# stepper_ctrl_v2.net
KiCad netlist of a schematic drawn in EAGLE
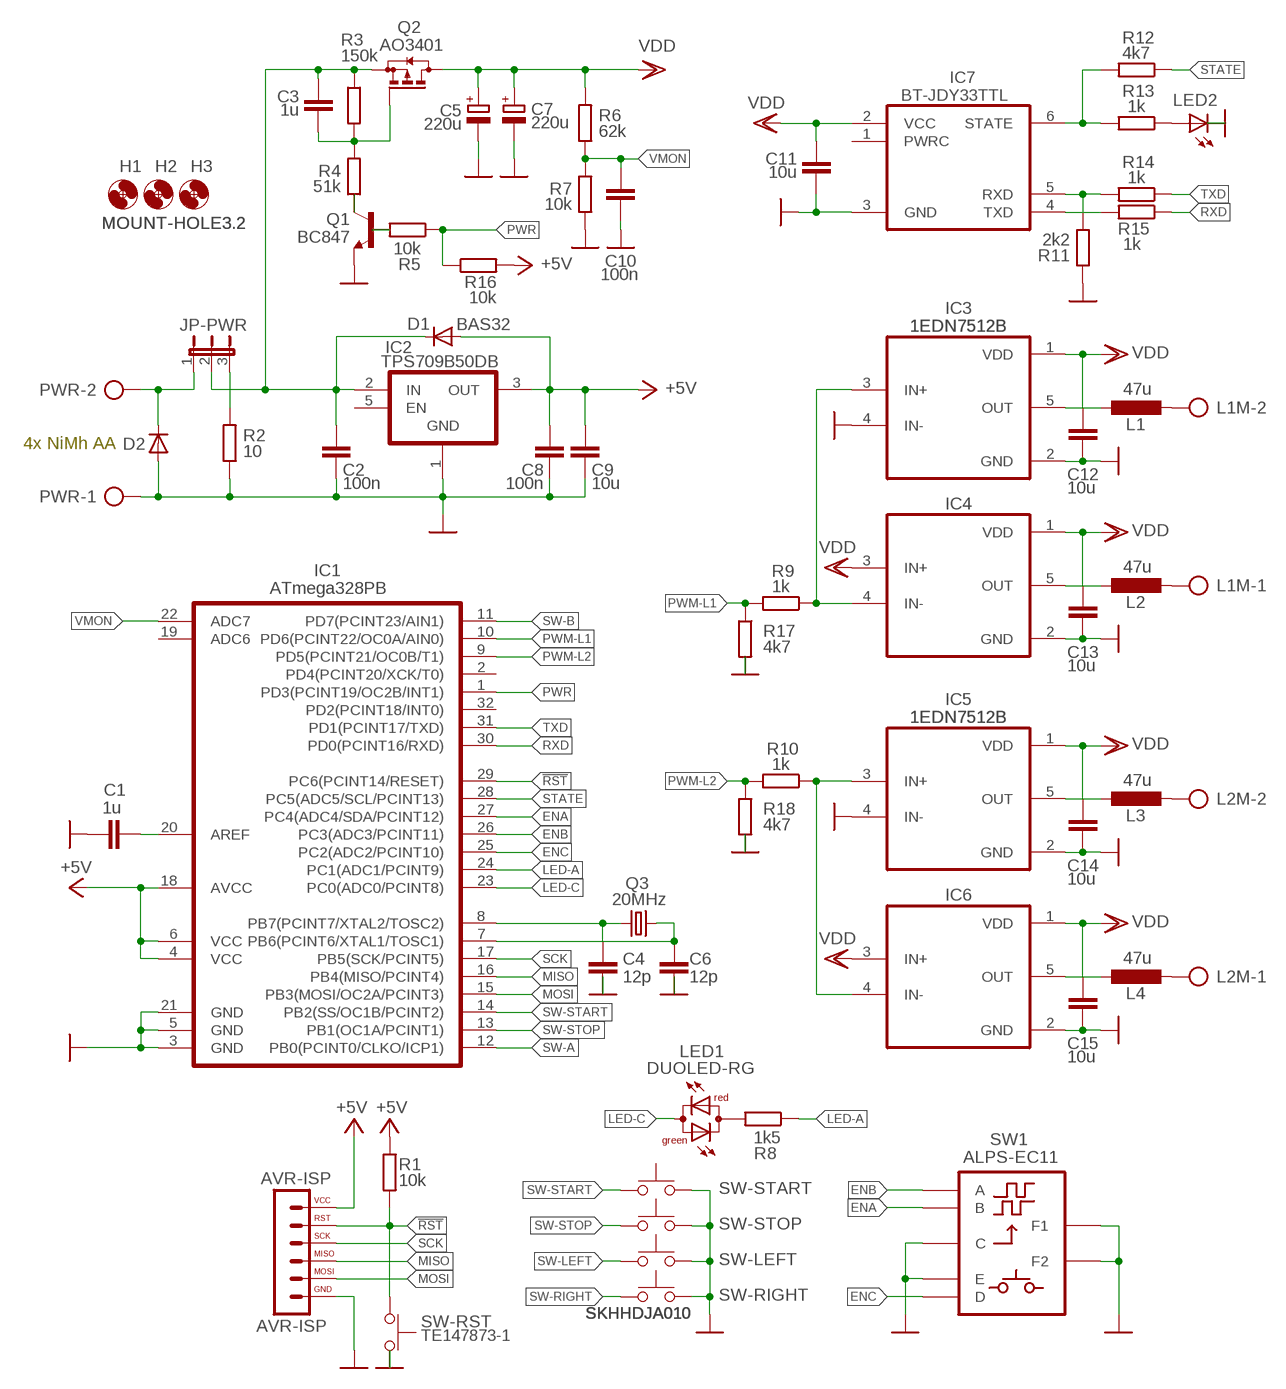
[diagram p0: schematic, sheet 1]

(export (version "E")
  (design (tool "Eeschema 10.0.6"))
  (components
    (comp (ref "AVR-ISP")
      (value "AVR-ISP")
      (footprint "eagle-import:SIL6-NNRND")
      (libsource (lib "eagle-import") (part "AVR_SPINR"))
    )
    (comp (ref "C1")
      (value "1u")
      (footprint "eagle-import:C0805K")
      (libsource (lib "eagle-import") (part "C-EUC0805K"))
    )
    (comp (ref "C2")
      (value "100n")
      (footprint "eagle-import:C0805K")
      (libsource (lib "eagle-import") (part "C-EUC0805K"))
    )
    (comp (ref "C3")
      (value "1u")
      (footprint "eagle-import:C0805K")
      (libsource (lib "eagle-import") (part "C-EUC0805K"))
    )
    (comp (ref "C4")
      (value "12p")
      (footprint "eagle-import:C0603K")
      (libsource (lib "eagle-import") (part "C-EUC0603K"))
    )
    (comp (ref "C5")
      (value "220u")
      (footprint "eagle-import:E2,5-6")
      (libsource (lib "eagle-import") (part "CPOL-EUE2.5-6"))
    )
    (comp (ref "C6")
      (value "12p")
      (footprint "eagle-import:C0603K")
      (libsource (lib "eagle-import") (part "C-EUC0603K"))
    )
    (comp (ref "C7")
      (value "220u")
      (footprint "eagle-import:E2,5-6")
      (libsource (lib "eagle-import") (part "CPOL-EUE2.5-6"))
    )
    (comp (ref "C8")
      (value "100n")
      (footprint "eagle-import:C0805K")
      (libsource (lib "eagle-import") (part "C-EUC0805K"))
    )
    (comp (ref "C9")
      (value "10u")
      (footprint "eagle-import:C0805K")
      (libsource (lib "eagle-import") (part "C-EUC0805K"))
    )
    (comp (ref "C10")
      (value "100n")
      (footprint "eagle-import:C0603K")
      (libsource (lib "eagle-import") (part "C-EUC0603K"))
    )
    (comp (ref "C11")
      (value "10u")
      (footprint "eagle-import:C0805K")
      (libsource (lib "eagle-import") (part "C-EUC0805K"))
    )
    (comp (ref "C12")
      (value "10u")
      (footprint "eagle-import:C0805K")
      (libsource (lib "eagle-import") (part "C-EUC0805K"))
    )
    (comp (ref "C13")
      (value "10u")
      (footprint "eagle-import:C0805K")
      (libsource (lib "eagle-import") (part "C-EUC0805K"))
    )
    (comp (ref "C14")
      (value "10u")
      (footprint "eagle-import:C0805K")
      (libsource (lib "eagle-import") (part "C-EUC0805K"))
    )
    (comp (ref "C15")
      (value "10u")
      (footprint "eagle-import:C0805K")
      (libsource (lib "eagle-import") (part "C-EUC0805K"))
    )
    (comp (ref "D1")
      (value "BAS32")
      (footprint "eagle-import:SOD80C")
      (libsource (lib "eagle-import") (part "BAS32"))
    )
    (comp (ref "D2")
      (value "DIODE-SMB")
      (footprint "eagle-import:SMB")
      (libsource (lib "eagle-import") (part "DIODE-SMB"))
    )
    (comp (ref "H1")
      (value "MOUNT-HOLE3.2")
      (footprint "eagle-import:3,2")
      (libsource (lib "eagle-import") (part "MOUNT-HOLE3.2"))
    )
    (comp (ref "H2")
      (value "MOUNT-HOLE3.2")
      (footprint "eagle-import:3,2")
      (libsource (lib "eagle-import") (part "MOUNT-HOLE3.2"))
    )
    (comp (ref "H3")
      (value "MOUNT-HOLE3.2")
      (footprint "eagle-import:3,2")
      (libsource (lib "eagle-import") (part "MOUNT-HOLE3.2"))
    )
    (comp (ref "IC1")
      (value "ATmega328PB")
      (footprint "eagle-import:TQFP32")
      (libsource (lib "eagle-import") (part "ATMEGA88T"))
    )
    (comp (ref "IC2")
      (value "TPS709B50DB")
      (footprint "eagle-import:SOT23-5")
      (libsource (lib "eagle-import") (part "TPS709DB-B50"))
    )
    (comp (ref "IC3")
      (value "1EDN7512B")
      (footprint "eagle-import:SOT23-5")
      (libsource (lib "eagle-import") (part "1EDN7512B"))
    )
    (comp (ref "IC4")
      (value "1EDN7512B")
      (footprint "eagle-import:SOT23-5")
      (libsource (lib "eagle-import") (part "1EDN7512B"))
    )
    (comp (ref "IC5")
      (value "1EDN7512B")
      (footprint "eagle-import:SOT23-5")
      (libsource (lib "eagle-import") (part "1EDN7512B"))
    )
    (comp (ref "IC6")
      (value "1EDN7512B")
      (footprint "eagle-import:SOT23-5")
      (libsource (lib "eagle-import") (part "1EDN7512B"))
    )
    (comp (ref "IC7")
      (value "BT-JDY33TTL")
      (footprint "eagle-import:BT-JFY33TTL")
      (libsource (lib "eagle-import") (part "BT-JDY33TTL"))
    )
    (comp (ref "JP-PWR")
      (value "JP2EB")
      (footprint "eagle-import:JP2YB")
      (libsource (lib "eagle-import") (part "JP2EB"))
    )
    (comp (ref "L1")
      (value "47u")
      (footprint "eagle-import:L4018")
      (libsource (lib "eagle-import") (part "L-EUL4018"))
    )
    (comp (ref "L1M")
      (value "AK500/2")
      (footprint "eagle-import:AK500_2")
      (libsource (lib "eagle-import") (part "AK500/2"))
    )
    (comp (ref "L2")
      (value "47u")
      (footprint "eagle-import:L4018")
      (libsource (lib "eagle-import") (part "L-EUL4018"))
    )
    (comp (ref "L2M")
      (value "AK500/2")
      (footprint "eagle-import:AK500_2")
      (libsource (lib "eagle-import") (part "AK500/2"))
    )
    (comp (ref "L3")
      (value "47u")
      (footprint "eagle-import:L4018")
      (libsource (lib "eagle-import") (part "L-EUL4018"))
    )
    (comp (ref "L4")
      (value "47u")
      (footprint "eagle-import:L4018")
      (libsource (lib "eagle-import") (part "L-EUL4018"))
    )
    (comp (ref "LED1")
      (value "DUOLED-RG")
      (footprint "eagle-import:LED3MM")
      (libsource (lib "eagle-import") (part "DUOLED-RG"))
    )
    (comp (ref "LED2")
      (value "LED3MM")
      (footprint "eagle-import:LED3MM")
      (libsource (lib "eagle-import") (part "LED3MM"))
    )
    (comp (ref "PWR")
      (value "AK500/2")
      (footprint "eagle-import:AK500_2")
      (libsource (lib "eagle-import") (part "AK500/2"))
    )
    (comp (ref "Q1")
      (value "BC847")
      (footprint "eagle-import:SOT23")
      (libsource (lib "eagle-import") (part "BC847SMDCLT1"))
    )
    (comp (ref "Q2")
      (value "AO3401")
      (footprint "eagle-import:SOT23")
      (libsource (lib "eagle-import") (part "BSS84"))
    )
    (comp (ref "Q3")
      (value "20MHz")
      (footprint "eagle-import:HC49U-V")
      (libsource (lib "eagle-import") (part "CRYSTALHC49U-V"))
    )
    (comp (ref "R1")
      (value "10k")
      (footprint "eagle-import:R0603")
      (libsource (lib "eagle-import") (part "R-EU_R0603"))
    )
    (comp (ref "R2")
      (value "10")
      (footprint "eagle-import:R0805")
      (libsource (lib "eagle-import") (part "R-EU_R0805"))
    )
    (comp (ref "R3")
      (value "150k")
      (footprint "eagle-import:R0603")
      (libsource (lib "eagle-import") (part "R-EU_R0603"))
    )
    (comp (ref "R4")
      (value "51k")
      (footprint "eagle-import:R0603")
      (libsource (lib "eagle-import") (part "R-EU_R0603"))
    )
    (comp (ref "R5")
      (value "10k")
      (footprint "eagle-import:R0603")
      (libsource (lib "eagle-import") (part "R-EU_R0603"))
    )
    (comp (ref "R6")
      (value "62k")
      (footprint "eagle-import:R0603")
      (libsource (lib "eagle-import") (part "R-EU_R0603"))
    )
    (comp (ref "R7")
      (value "10k")
      (footprint "eagle-import:R0603")
      (libsource (lib "eagle-import") (part "R-EU_R0603"))
    )
    (comp (ref "R8")
      (value "1k5")
      (footprint "eagle-import:R0603")
      (libsource (lib "eagle-import") (part "R-EU_R0603"))
    )
    (comp (ref "R9")
      (value "1k")
      (footprint "eagle-import:R0603")
      (libsource (lib "eagle-import") (part "R-EU_R0603"))
    )
    (comp (ref "R10")
      (value "1k")
      (footprint "eagle-import:R0603")
      (libsource (lib "eagle-import") (part "R-EU_R0603"))
    )
    (comp (ref "R11")
      (value "2k2")
      (footprint "eagle-import:R0603")
      (libsource (lib "eagle-import") (part "R-EU_R0603"))
    )
    (comp (ref "R12")
      (value "4k7")
      (footprint "eagle-import:R0603")
      (libsource (lib "eagle-import") (part "R-EU_R0603"))
    )
    (comp (ref "R13")
      (value "1k")
      (footprint "eagle-import:R0603")
      (libsource (lib "eagle-import") (part "R-EU_R0603"))
    )
    (comp (ref "R14")
      (value "1k")
      (footprint "eagle-import:R0603")
      (libsource (lib "eagle-import") (part "R-EU_R0603"))
    )
    (comp (ref "R15")
      (value "1k")
      (footprint "eagle-import:R0603")
      (libsource (lib "eagle-import") (part "R-EU_R0603"))
    )
    (comp (ref "R16")
      (value "10k")
      (footprint "eagle-import:R0603")
      (libsource (lib "eagle-import") (part "R-EU_R0603"))
    )
    (comp (ref "R17")
      (value "4k7")
      (footprint "eagle-import:R0603")
      (libsource (lib "eagle-import") (part "R-EU_R0603"))
    )
    (comp (ref "R18")
      (value "4k7")
      (footprint "eagle-import:R0603")
      (libsource (lib "eagle-import") (part "R-EU_R0603"))
    )
    (comp (ref "SW-LEFT")
      (value "SKHHDJA010")
      (footprint "eagle-import:CUDL1")
      (libsource (lib "eagle-import") (part "CUDL1_A"))
    )
    (comp (ref "SW-RIGHT")
      (value "SKHHDJA010")
      (footprint "eagle-import:CUDL1")
      (libsource (lib "eagle-import") (part "CUDL1_A"))
    )
    (comp (ref "SW-RST")
      (value "TE147873-1")
      (footprint "eagle-import:TE-147873-1")
      (libsource (lib "eagle-import") (part "CUDL1TE147873-1"))
    )
    (comp (ref "SW-START")
      (value "SKHHDJA010")
      (footprint "eagle-import:CUDL1")
      (libsource (lib "eagle-import") (part "CUDL1_A"))
    )
    (comp (ref "SW-STOP")
      (value "SKHHDJA010")
      (footprint "eagle-import:CUDL1")
      (libsource (lib "eagle-import") (part "CUDL1_A"))
    )
    (comp (ref "SW1")
      (value "ALPS-EC11")
      (footprint "eagle-import:ALPS_EC11")
      (libsource (lib "eagle-import") (part "ALPS_EC11"))
    )
  )
  (nets
    (net (code "1") (name "+5V") (class "Default")
      (node (ref "AVR-ISP") (pin "6") (pinfunction "6_6") (pintype "passive"))
      (node (ref "C8") (pin "1") (pinfunction "1_1") (pintype "passive"))
      (node (ref "C9") (pin "1") (pinfunction "1_1") (pintype "passive"))
      (node (ref "D1") (pin "A") (pinfunction "A_A") (pintype "passive"))
      (node (ref "IC1") (pin "18") (pinfunction "AVCC_18") (pintype "power_in"))
      (node (ref "IC1") (pin "4") (pinfunction "VCC_4") (pintype "power_in"))
      (node (ref "IC1") (pin "6") (pinfunction "VCC_6") (pintype "power_in"))
      (node (ref "IC2") (pin "3") (pinfunction "OUT_3") (pintype "passive"))
      (node (ref "R1") (pin "1") (pinfunction "1_1") (pintype "passive"))
      (node (ref "R16") (pin "2") (pinfunction "2_2") (pintype "passive"))
    )
    (net (code "2") (name "/~{RST}") (class "Default")
      (node (ref "AVR-ISP") (pin "5") (pinfunction "5_5") (pintype "passive"))
      (node (ref "IC1") (pin "29") (pinfunction "PC6(PCINT14/RESET)_29") (pintype "bidirectional"))
      (node (ref "R1") (pin "2") (pinfunction "2_2") (pintype "passive"))
      (node (ref "SW-RST") (pin "P$2") (pinfunction "P$2_P$2") (pintype "passive"))
    )
    (net (code "3") (name "ENA") (class "Default")
      (node (ref "IC1") (pin "27") (pinfunction "PC4(ADC4/SDA/PCINT12)_27") (pintype "bidirectional"))
      (node (ref "SW1") (pin "B") (pinfunction "B_B") (pintype "passive"))
    )
    (net (code "4") (name "ENB") (class "Default")
      (node (ref "IC1") (pin "26") (pinfunction "PC3(ADC3/PCINT11)_26") (pintype "bidirectional"))
      (node (ref "SW1") (pin "A") (pinfunction "A_A") (pintype "passive"))
    )
    (net (code "5") (name "ENC") (class "Default")
      (node (ref "IC1") (pin "25") (pinfunction "PC2(ADC2/PCINT10)_25") (pintype "bidirectional"))
      (node (ref "SW1") (pin "D") (pinfunction "D_D") (pintype "passive"))
    )
    (net (code "6") (name "GND") (class "Default")
      (node (ref "AVR-ISP") (pin "1") (pinfunction "1_1") (pintype "passive"))
      (node (ref "C1") (pin "1") (pinfunction "1_1") (pintype "passive"))
      (node (ref "C10") (pin "2") (pinfunction "2_2") (pintype "passive"))
      (node (ref "C11") (pin "2") (pinfunction "2_2") (pintype "passive"))
      (node (ref "C12") (pin "2") (pinfunction "2_2") (pintype "passive"))
      (node (ref "C13") (pin "2") (pinfunction "2_2") (pintype "passive"))
      (node (ref "C14") (pin "2") (pinfunction "2_2") (pintype "passive"))
      (node (ref "C15") (pin "2") (pinfunction "2_2") (pintype "passive"))
      (node (ref "C2") (pin "2") (pinfunction "2_2") (pintype "passive"))
      (node (ref "C4") (pin "2") (pinfunction "2_2") (pintype "passive"))
      (node (ref "C5") (pin "-") (pinfunction "-_-") (pintype "passive"))
      (node (ref "C6") (pin "2") (pinfunction "2_2") (pintype "passive"))
      (node (ref "C7") (pin "-") (pinfunction "-_-") (pintype "passive"))
      (node (ref "C8") (pin "2") (pinfunction "2_2") (pintype "passive"))
      (node (ref "C9") (pin "2") (pinfunction "2_2") (pintype "passive"))
      (node (ref "D2") (pin "A") (pinfunction "A_A") (pintype "passive"))
      (node (ref "IC1") (pin "21") (pinfunction "GND_21") (pintype "power_in"))
      (node (ref "IC1") (pin "3") (pinfunction "GND_3") (pintype "power_in"))
      (node (ref "IC1") (pin "5") (pinfunction "GND_5") (pintype "power_in"))
      (node (ref "IC2") (pin "1") (pinfunction "GND_1") (pintype "passive"))
      (node (ref "IC3") (pin "2") (pinfunction "GND_2") (pintype "passive"))
      (node (ref "IC3") (pin "4") (pinfunction "IN-_4") (pintype "input"))
      (node (ref "IC4") (pin "2") (pinfunction "GND_2") (pintype "passive"))
      (node (ref "IC5") (pin "2") (pinfunction "GND_2") (pintype "passive"))
      (node (ref "IC5") (pin "4") (pinfunction "IN-_4") (pintype "input"))
      (node (ref "IC6") (pin "2") (pinfunction "GND_2") (pintype "passive"))
      (node (ref "IC7") (pin "3") (pinfunction "GND_3") (pintype "passive"))
      (node (ref "LED2") (pin "K") (pinfunction "C_K") (pintype "passive"))
      (node (ref "PWR") (pin "1") (pinfunction "KL_1") (pintype "passive"))
      (node (ref "Q1") (pin "2") (pinfunction "E_2") (pintype "passive"))
      (node (ref "R11") (pin "2") (pinfunction "2_2") (pintype "passive"))
      (node (ref "R17") (pin "2") (pinfunction "2_2") (pintype "passive"))
      (node (ref "R18") (pin "2") (pinfunction "2_2") (pintype "passive"))
      (node (ref "R2") (pin "1") (pinfunction "1_1") (pintype "passive"))
      (node (ref "R7") (pin "1") (pinfunction "1_1") (pintype "passive"))
      (node (ref "SW-LEFT") (pin "1") (pinfunction "P$1_1") (pintype "passive"))
      (node (ref "SW-LEFT") (pin "2") (pinfunction "P$1_2") (pintype "passive"))
      (node (ref "SW-RIGHT") (pin "1") (pinfunction "P$1_1") (pintype "passive"))
      (node (ref "SW-RIGHT") (pin "2") (pinfunction "P$1_2") (pintype "passive"))
      (node (ref "SW-RST") (pin "P$1") (pinfunction "P$1_P$1") (pintype "passive"))
      (node (ref "SW-START") (pin "1") (pinfunction "P$1_1") (pintype "passive"))
      (node (ref "SW-START") (pin "2") (pinfunction "P$1_2") (pintype "passive"))
      (node (ref "SW-STOP") (pin "1") (pinfunction "P$1_1") (pintype "passive"))
      (node (ref "SW-STOP") (pin "2") (pinfunction "P$1_2") (pintype "passive"))
      (node (ref "SW1") (pin "C") (pinfunction "C_C") (pintype "passive"))
      (node (ref "SW1") (pin "E") (pinfunction "E_E") (pintype "passive"))
      (node (ref "SW1") (pin "F1") (pinfunction "F1_F1") (pintype "passive"))
      (node (ref "SW1") (pin "F2") (pinfunction "F2_F2") (pintype "passive"))
    )
    (net (code "7") (name "LED-A") (class "Default")
      (node (ref "IC1") (pin "24") (pinfunction "PC1(ADC1/PCINT9)_24") (pintype "bidirectional"))
      (node (ref "R8") (pin "1") (pinfunction "1_1") (pintype "passive"))
    )
    (net (code "8") (name "LED-C") (class "Default")
      (node (ref "IC1") (pin "23") (pinfunction "PC0(ADC0/PCINT8)_23") (pintype "bidirectional"))
      (node (ref "LED1") (pin "K") (pinfunction "C_K") (pintype "passive"))
    )
    (net (code "9") (name "MISO") (class "Default")
      (node (ref "AVR-ISP") (pin "3") (pinfunction "3_3") (pintype "passive"))
      (node (ref "IC1") (pin "16") (pinfunction "PB4(MISO/PCINT4)_16") (pintype "bidirectional"))
    )
    (net (code "10") (name "MOSI") (class "Default")
      (node (ref "AVR-ISP") (pin "2") (pinfunction "2_2") (pintype "passive"))
      (node (ref "IC1") (pin "15") (pinfunction "PB3(MOSI/OC2A/PCINT3)_15") (pintype "bidirectional"))
    )
    (net (code "11") (name "Net-(IC1-AREF)") (class "Default")
      (node (ref "C1") (pin "2") (pinfunction "2_2") (pintype "passive"))
      (node (ref "IC1") (pin "20") (pinfunction "AREF_20") (pintype "input"))
    )
    (net (code "12") (name "Net-(IC1-PB6(PCINT6{slash}XTAL1{slash}TOSC1))") (class "Default")
      (node (ref "C6") (pin "1") (pinfunction "1_1") (pintype "passive"))
      (node (ref "IC1") (pin "7") (pinfunction "PB6(PCINT6/XTAL1/TOSC1)_7") (pintype "bidirectional"))
      (node (ref "Q3") (pin "2") (pinfunction "2_2") (pintype "passive"))
    )
    (net (code "13") (name "Net-(IC1-PB7(PCINT7{slash}XTAL2{slash}TOSC2))") (class "Default")
      (node (ref "C4") (pin "1") (pinfunction "1_1") (pintype "passive"))
      (node (ref "IC1") (pin "8") (pinfunction "PB7(PCINT7/XTAL2/TOSC2)_8") (pintype "bidirectional"))
      (node (ref "Q3") (pin "1") (pinfunction "1_1") (pintype "passive"))
    )
    (net (code "14") (name "Net-(IC2-IN)") (class "Default")
      (node (ref "C2") (pin "1") (pinfunction "1_1") (pintype "passive"))
      (node (ref "C3") (pin "1") (pinfunction "1_1") (pintype "passive"))
      (node (ref "D1") (pin "C") (pinfunction "C_C") (pintype "passive"))
      (node (ref "IC2") (pin "2") (pinfunction "IN_2") (pintype "passive"))
      (node (ref "JP-PWR") (pin "2") (pinfunction "2_2") (pintype "passive"))
      (node (ref "Q2") (pin "2") (pinfunction "S_2") (pintype "passive"))
      (node (ref "R3") (pin "1") (pinfunction "1_1") (pintype "passive"))
    )
    (net (code "15") (name "Net-(IC3-IN+)") (class "Default")
      (node (ref "IC3") (pin "3") (pinfunction "IN+_3") (pintype "input"))
      (node (ref "IC4") (pin "4") (pinfunction "IN-_4") (pintype "input"))
      (node (ref "R9") (pin "1") (pinfunction "1_1") (pintype "passive"))
    )
    (net (code "16") (name "Net-(IC3-OUT)") (class "Default")
      (node (ref "IC3") (pin "5") (pinfunction "OUT_5") (pintype "passive"))
      (node (ref "L1") (pin "2") (pinfunction "2_2") (pintype "passive"))
    )
    (net (code "17") (name "Net-(IC4-OUT)") (class "Default")
      (node (ref "IC4") (pin "5") (pinfunction "OUT_5") (pintype "passive"))
      (node (ref "L2") (pin "2") (pinfunction "2_2") (pintype "passive"))
    )
    (net (code "18") (name "Net-(IC5-IN+)") (class "Default")
      (node (ref "IC5") (pin "3") (pinfunction "IN+_3") (pintype "input"))
      (node (ref "IC6") (pin "4") (pinfunction "IN-_4") (pintype "input"))
      (node (ref "R10") (pin "1") (pinfunction "1_1") (pintype "passive"))
    )
    (net (code "19") (name "Net-(IC5-OUT)") (class "Default")
      (node (ref "IC5") (pin "5") (pinfunction "OUT_5") (pintype "passive"))
      (node (ref "L3") (pin "2") (pinfunction "2_2") (pintype "passive"))
    )
    (net (code "20") (name "Net-(IC6-OUT)") (class "Default")
      (node (ref "IC6") (pin "5") (pinfunction "OUT_5") (pintype "passive"))
      (node (ref "L4") (pin "2") (pinfunction "2_2") (pintype "passive"))
    )
    (net (code "21") (name "Net-(IC7-RXD)") (class "Default")
      (node (ref "IC7") (pin "5") (pinfunction "RXD_5") (pintype "input"))
      (node (ref "R11") (pin "1") (pinfunction "1_1") (pintype "passive"))
      (node (ref "R14") (pin "2") (pinfunction "2_2") (pintype "passive"))
    )
    (net (code "22") (name "Net-(IC7-STATE)") (class "Default")
      (node (ref "IC7") (pin "6") (pinfunction "STATE_6") (pintype "output"))
      (node (ref "R12") (pin "2") (pinfunction "2_2") (pintype "passive"))
      (node (ref "R13") (pin "2") (pinfunction "2_2") (pintype "passive"))
    )
    (net (code "23") (name "Net-(IC7-TXD)") (class "Default")
      (node (ref "IC7") (pin "4") (pinfunction "TXD_4") (pintype "output"))
      (node (ref "R15") (pin "2") (pinfunction "2_2") (pintype "passive"))
    )
    (net (code "24") (name "Net-(JP-PWR-Pad3)") (class "Default")
      (node (ref "JP-PWR") (pin "3") (pinfunction "3_3") (pintype "passive"))
      (node (ref "R2") (pin "2") (pinfunction "2_2") (pintype "passive"))
    )
    (net (code "25") (name "Net-(L1MA-KL)") (class "Default")
      (node (ref "L1M") (pin "1") (pinfunction "KL_1") (pintype "passive"))
      (node (ref "L2") (pin "1") (pinfunction "1_1") (pintype "passive"))
    )
    (net (code "26") (name "Net-(L1MB-KL)") (class "Default")
      (node (ref "L1") (pin "1") (pinfunction "1_1") (pintype "passive"))
      (node (ref "L1M") (pin "2") (pinfunction "KL_2") (pintype "passive"))
    )
    (net (code "27") (name "Net-(L2MA-KL)") (class "Default")
      (node (ref "L2M") (pin "1") (pinfunction "KL_1") (pintype "passive"))
      (node (ref "L4") (pin "1") (pinfunction "1_1") (pintype "passive"))
    )
    (net (code "28") (name "Net-(L2MB-KL)") (class "Default")
      (node (ref "L2M") (pin "2") (pinfunction "KL_2") (pintype "passive"))
      (node (ref "L3") (pin "1") (pinfunction "1_1") (pintype "passive"))
    )
    (net (code "29") (name "Net-(LED1-PadA)") (class "Default")
      (node (ref "LED1") (pin "A") (pinfunction "A_A") (pintype "passive"))
      (node (ref "R8") (pin "2") (pinfunction "2_2") (pintype "passive"))
    )
    (net (code "30") (name "Net-(LED2-PadA)") (class "Default")
      (node (ref "LED2") (pin "A") (pinfunction "A_A") (pintype "passive"))
      (node (ref "R13") (pin "1") (pinfunction "1_1") (pintype "passive"))
    )
    (net (code "31") (name "Net-(PWRB-KL)") (class "Default")
      (node (ref "D2") (pin "C") (pinfunction "C_C") (pintype "passive"))
      (node (ref "JP-PWR") (pin "1") (pinfunction "1_1") (pintype "passive"))
      (node (ref "PWR") (pin "2") (pinfunction "KL_2") (pintype "passive"))
    )
    (net (code "32") (name "Net-(Q1-B)") (class "Default")
      (node (ref "Q1") (pin "1") (pinfunction "B_1") (pintype "passive"))
      (node (ref "R5") (pin "2") (pinfunction "2_2") (pintype "passive"))
    )
    (net (code "33") (name "Net-(Q1-C)") (class "Default")
      (node (ref "Q1") (pin "3") (pinfunction "C_3") (pintype "passive"))
      (node (ref "R4") (pin "1") (pinfunction "1_1") (pintype "passive"))
    )
    (net (code "34") (name "Net-(Q2-G)") (class "Default")
      (node (ref "C3") (pin "2") (pinfunction "2_2") (pintype "passive"))
      (node (ref "Q2") (pin "1") (pinfunction "G_1") (pintype "passive"))
      (node (ref "R3") (pin "2") (pinfunction "2_2") (pintype "passive"))
      (node (ref "R4") (pin "2") (pinfunction "2_2") (pintype "passive"))
    )
    (net (code "35") (name "PWM-L1") (class "Default")
      (node (ref "IC1") (pin "10") (pinfunction "PD6(PCINT22/OC0A/AIN0)_10") (pintype "bidirectional"))
      (node (ref "R17") (pin "1") (pinfunction "1_1") (pintype "passive"))
      (node (ref "R9") (pin "2") (pinfunction "2_2") (pintype "passive"))
    )
    (net (code "36") (name "PWM-L2") (class "Default")
      (node (ref "IC1") (pin "9") (pinfunction "PD5(PCINT21/OC0B/T1)_9") (pintype "bidirectional"))
      (node (ref "R10") (pin "2") (pinfunction "2_2") (pintype "passive"))
      (node (ref "R18") (pin "1") (pinfunction "1_1") (pintype "passive"))
    )
    (net (code "37") (name "PWR") (class "Default")
      (node (ref "IC1") (pin "1") (pinfunction "PD3(PCINT19/OC2B/INT1)_1") (pintype "bidirectional"))
      (node (ref "R16") (pin "1") (pinfunction "1_1") (pintype "passive"))
      (node (ref "R5") (pin "1") (pinfunction "1_1") (pintype "passive"))
    )
    (net (code "38") (name "RXD") (class "Default")
      (node (ref "IC1") (pin "30") (pinfunction "PD0(PCINT16/RXD)_30") (pintype "bidirectional"))
      (node (ref "R15") (pin "1") (pinfunction "1_1") (pintype "passive"))
    )
    (net (code "39") (name "SCK") (class "Default")
      (node (ref "AVR-ISP") (pin "4") (pinfunction "4_4") (pintype "passive"))
      (node (ref "IC1") (pin "17") (pinfunction "PB5(SCK/PCINT5)_17") (pintype "bidirectional"))
    )
    (net (code "40") (name "STATE") (class "Default")
      (node (ref "IC1") (pin "28") (pinfunction "PC5(ADC5/SCL/PCINT13)_28") (pintype "bidirectional"))
      (node (ref "R12") (pin "1") (pinfunction "1_1") (pintype "passive"))
    )
    (net (code "41") (name "SW-A") (class "Default")
      (node (ref "IC1") (pin "12") (pinfunction "PB0(PCINT0/CLKO/ICP1)_12") (pintype "bidirectional"))
    )
    (net (code "42") (name "SW-B") (class "Default")
      (node (ref "IC1") (pin "11") (pinfunction "PD7(PCINT23/AIN1)_11") (pintype "bidirectional"))
    )
    (net (code "43") (name "SW-LEFT") (class "Default")
      (node (ref "SW-LEFT") (pin "3") (pinfunction "P$2_3") (pintype "passive"))
      (node (ref "SW-LEFT") (pin "4") (pinfunction "P$2_4") (pintype "passive"))
    )
    (net (code "44") (name "SW-RIGHT") (class "Default")
      (node (ref "SW-RIGHT") (pin "3") (pinfunction "P$2_3") (pintype "passive"))
      (node (ref "SW-RIGHT") (pin "4") (pinfunction "P$2_4") (pintype "passive"))
    )
    (net (code "45") (name "SW-START") (class "Default")
      (node (ref "IC1") (pin "14") (pinfunction "PB2(SS/OC1B/PCINT2)_14") (pintype "bidirectional"))
      (node (ref "SW-START") (pin "3") (pinfunction "P$2_3") (pintype "passive"))
      (node (ref "SW-START") (pin "4") (pinfunction "P$2_4") (pintype "passive"))
    )
    (net (code "46") (name "SW-STOP") (class "Default")
      (node (ref "IC1") (pin "13") (pinfunction "PB1(OC1A/PCINT1)_13") (pintype "bidirectional"))
      (node (ref "SW-STOP") (pin "3") (pinfunction "P$2_3") (pintype "passive"))
      (node (ref "SW-STOP") (pin "4") (pinfunction "P$2_4") (pintype "passive"))
    )
    (net (code "47") (name "TXD") (class "Default")
      (node (ref "IC1") (pin "31") (pinfunction "PD1(PCINT17/TXD)_31") (pintype "bidirectional"))
      (node (ref "R14") (pin "1") (pinfunction "1_1") (pintype "passive"))
    )
    (net (code "48") (name "VDD") (class "Default")
      (node (ref "C11") (pin "1") (pinfunction "1_1") (pintype "passive"))
      (node (ref "C12") (pin "1") (pinfunction "1_1") (pintype "passive"))
      (node (ref "C13") (pin "1") (pinfunction "1_1") (pintype "passive"))
      (node (ref "C14") (pin "1") (pinfunction "1_1") (pintype "passive"))
      (node (ref "C15") (pin "1") (pinfunction "1_1") (pintype "passive"))
      (node (ref "C5") (pin "+") (pinfunction "+_+") (pintype "passive"))
      (node (ref "C7") (pin "+") (pinfunction "+_+") (pintype "passive"))
      (node (ref "IC3") (pin "1") (pinfunction "VDD_1") (pintype "passive"))
      (node (ref "IC4") (pin "1") (pinfunction "VDD_1") (pintype "passive"))
      (node (ref "IC4") (pin "3") (pinfunction "IN+_3") (pintype "input"))
      (node (ref "IC5") (pin "1") (pinfunction "VDD_1") (pintype "passive"))
      (node (ref "IC6") (pin "1") (pinfunction "VDD_1") (pintype "passive"))
      (node (ref "IC6") (pin "3") (pinfunction "IN+_3") (pintype "input"))
      (node (ref "IC7") (pin "2") (pinfunction "VCC_2") (pintype "passive"))
      (node (ref "Q2") (pin "3") (pinfunction "D_3") (pintype "passive"))
      (node (ref "R6") (pin "2") (pinfunction "2_2") (pintype "passive"))
    )
    (net (code "49") (name "VMON") (class "Default")
      (node (ref "C10") (pin "1") (pinfunction "1_1") (pintype "passive"))
      (node (ref "IC1") (pin "22") (pinfunction "ADC7_22") (pintype "bidirectional"))
      (node (ref "R6") (pin "1") (pinfunction "1_1") (pintype "passive"))
      (node (ref "R7") (pin "2") (pinfunction "2_2") (pintype "passive"))
    )
    (net (code "50") (name "unconnected-(IC1-ADC6-Pad19)") (class "Default")
      (node (ref "IC1") (pin "19") (pinfunction "ADC6_19") (pintype "bidirectional"))
    )
    (net (code "51") (name "unconnected-(IC1-PD2(PCINT18{slash}INT0)-Pad32)") (class "Default")
      (node (ref "IC1") (pin "32") (pinfunction "PD2(PCINT18/INT0)_32") (pintype "bidirectional"))
    )
    (net (code "52") (name "unconnected-(IC1-PD4(PCINT20{slash}XCK{slash}T0)-Pad2)") (class "Default")
      (node (ref "IC1") (pin "2") (pinfunction "PD4(PCINT20/XCK/T0)_2") (pintype "bidirectional"))
    )
    (net (code "53") (name "unconnected-(IC2-EN-Pad5)") (class "Default")
      (node (ref "IC2") (pin "5") (pinfunction "EN_5") (pintype "input"))
    )
    (net (code "54") (name "unconnected-(IC7-PWRC-Pad1)") (class "Default")
      (node (ref "IC7") (pin "1") (pinfunction "PWRC_1") (pintype "passive"))
    )
  )
)
